# AguaC.net
KiCad netlist of a schematic drawn in EAGLE
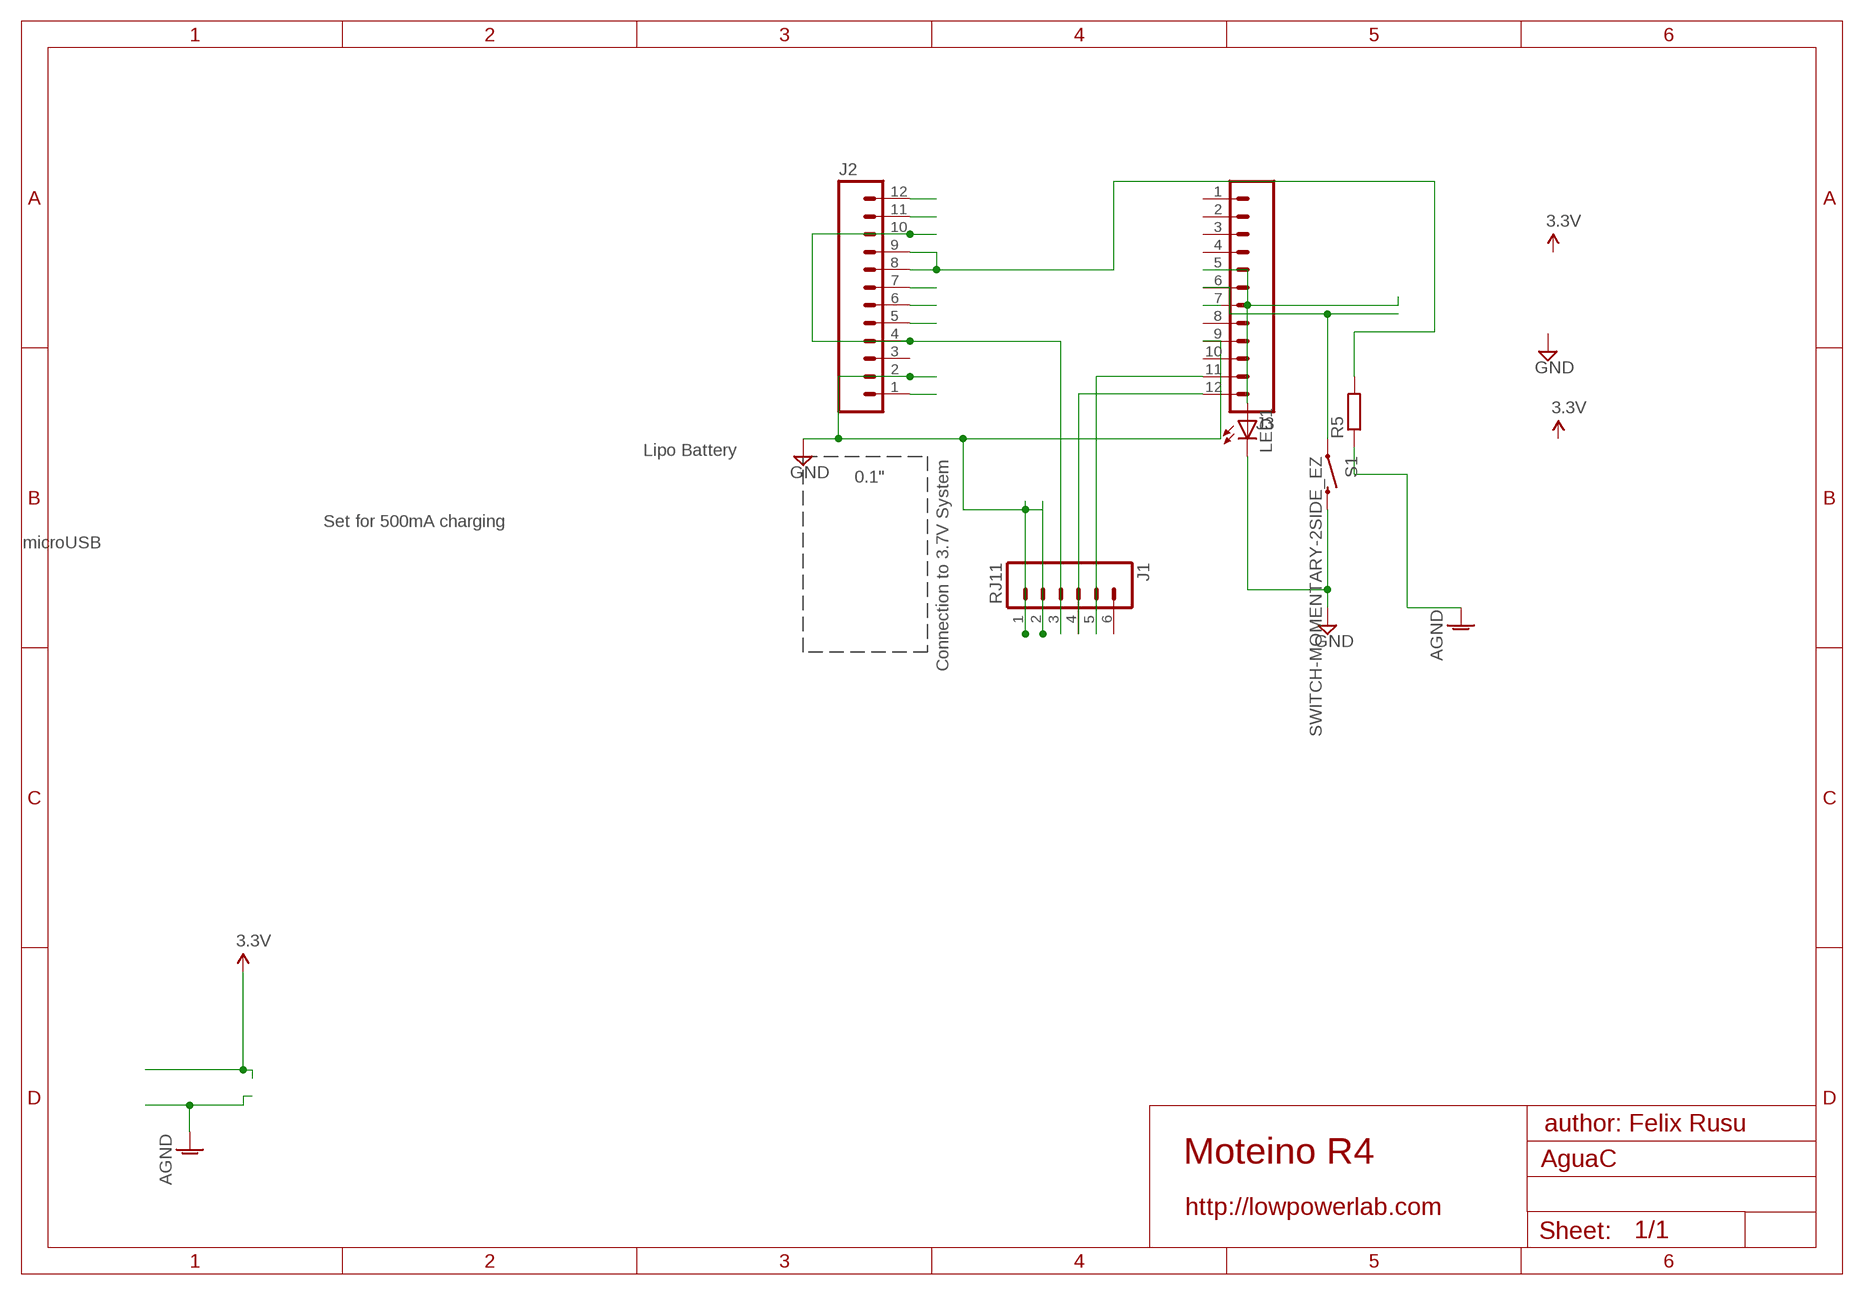
[diagram p0: schematic, sheet 1]

(export (version "E")
  (design (tool "Eeschema 10.0.6"))
  (components
    (comp (ref "J1")
      (value "RJ11")
      (footprint "eagle-import:RJ11-6")
      (libsource (lib "eagle-import") (part "RJ11-6PTH"))
    )
    (comp (ref "J2")
      (value "M12PTH")
      (footprint "eagle-import:1X12")
      (libsource (lib "eagle-import") (part "M12PTH"))
    )
    (comp (ref "J3")
      (value "M12PTH")
      (footprint "eagle-import:1X12")
      (libsource (lib "eagle-import") (part "M12PTH"))
    )
    (comp (ref "LED1")
      (value "LED3MM")
      (footprint "eagle-import:LED3MM")
      (libsource (lib "eagle-import") (part "LED3MM"))
    )
    (comp (ref "R5")
      (value "R-EU_0204/7")
      (footprint "eagle-import:0204_7")
      (libsource (lib "eagle-import") (part "R-EU_0204/7"))
    )
    (comp (ref "S1")
      (value "SWITCH-MOMENTARY-2SIDE_EZ")
      (footprint "eagle-import:TACTILE-PTH-SIDEEZ")
      (libsource (lib "eagle-import") (part "SWITCH-MOMENTARY-2SIDE_EZ"))
    )
  )
  (nets
    (net (code "2") (name "AGND") (class "Default")
      (node (ref "R5") (pin "1") (pinfunction "1_1") (pintype "passive"))
    )
    (net (code "3") (name "GND") (class "Default")
      (node (ref "J1") (pin "1") (pinfunction "1_1") (pintype "passive"))
      (node (ref "J1") (pin "2") (pinfunction "2_2") (pintype "passive"))
      (node (ref "J2") (pin "2") (pinfunction "2_2") (pintype "passive"))
      (node (ref "J3") (pin "9") (pinfunction "9_9") (pintype "passive"))
      (node (ref "LED1") (pin "K") (pinfunction "C_K") (pintype "passive"))
      (node (ref "S1") (pin "2") (pinfunction "2_2") (pintype "passive"))
    )
    (net (code "4") (name "Net-(J1-Pad3)") (class "Default")
      (node (ref "J1") (pin "3") (pinfunction "3_3") (pintype "passive"))
      (node (ref "J2") (pin "10") (pinfunction "10_10") (pintype "passive"))
      (node (ref "J2") (pin "4") (pinfunction "4_4") (pintype "passive"))
    )
    (net (code "5") (name "Net-(J1-Pad4)") (class "Default")
      (node (ref "J1") (pin "4") (pinfunction "4_4") (pintype "passive"))
      (node (ref "J3") (pin "12") (pinfunction "12_12") (pintype "passive"))
    )
    (net (code "6") (name "Net-(J1-Pad5)") (class "Default")
      (node (ref "J1") (pin "5") (pinfunction "5_5") (pintype "passive"))
      (node (ref "J3") (pin "11") (pinfunction "11_11") (pintype "passive"))
    )
    (net (code "7") (name "Net-(J2-Pad8)") (class "Default")
      (node (ref "J2") (pin "8") (pinfunction "8_8") (pintype "passive"))
      (node (ref "J2") (pin "9") (pinfunction "9_9") (pintype "passive"))
      (node (ref "R5") (pin "2") (pinfunction "2_2") (pintype "passive"))
    )
    (net (code "8") (name "Net-(J3-Pad5)") (class "Default")
      (node (ref "J3") (pin "5") (pinfunction "5_5") (pintype "passive"))
      (node (ref "LED1") (pin "A") (pinfunction "A_A") (pintype "passive"))
    )
    (net (code "9") (name "Net-(J3-Pad6)") (class "Default")
      (node (ref "J3") (pin "6") (pinfunction "6_6") (pintype "passive"))
      (node (ref "S1") (pin "1") (pinfunction "1_1") (pintype "passive"))
    )
    (net (code "10") (name "unconnected-(J1-Pad6)") (class "Default")
      (node (ref "J1") (pin "6") (pinfunction "6_6") (pintype "passive"))
    )
    (net (code "11") (name "unconnected-(J2-Pad1)") (class "Default")
      (node (ref "J2") (pin "1") (pinfunction "1_1") (pintype "passive"))
    )
    (net (code "12") (name "unconnected-(J2-Pad3)") (class "Default")
      (node (ref "J2") (pin "3") (pinfunction "3_3") (pintype "passive"))
    )
    (net (code "13") (name "unconnected-(J2-Pad5)") (class "Default")
      (node (ref "J2") (pin "5") (pinfunction "5_5") (pintype "passive"))
    )
    (net (code "14") (name "unconnected-(J2-Pad6)") (class "Default")
      (node (ref "J2") (pin "6") (pinfunction "6_6") (pintype "passive"))
    )
    (net (code "15") (name "unconnected-(J2-Pad7)") (class "Default")
      (node (ref "J2") (pin "7") (pinfunction "7_7") (pintype "passive"))
    )
    (net (code "16") (name "unconnected-(J2-Pad11)") (class "Default")
      (node (ref "J2") (pin "11") (pinfunction "11_11") (pintype "passive"))
    )
    (net (code "17") (name "unconnected-(J2-Pad12)") (class "Default")
      (node (ref "J2") (pin "12") (pinfunction "12_12") (pintype "passive"))
    )
    (net (code "18") (name "unconnected-(J3-Pad1)") (class "Default")
      (node (ref "J3") (pin "1") (pinfunction "1_1") (pintype "passive"))
    )
    (net (code "19") (name "unconnected-(J3-Pad2)") (class "Default")
      (node (ref "J3") (pin "2") (pinfunction "2_2") (pintype "passive"))
    )
    (net (code "20") (name "unconnected-(J3-Pad3)") (class "Default")
      (node (ref "J3") (pin "3") (pinfunction "3_3") (pintype "passive"))
    )
    (net (code "21") (name "unconnected-(J3-Pad4)") (class "Default")
      (node (ref "J3") (pin "4") (pinfunction "4_4") (pintype "passive"))
    )
    (net (code "22") (name "unconnected-(J3-Pad7)") (class "Default")
      (node (ref "J3") (pin "7") (pinfunction "7_7") (pintype "passive"))
    )
    (net (code "23") (name "unconnected-(J3-Pad8)") (class "Default")
      (node (ref "J3") (pin "8") (pinfunction "8_8") (pintype "passive"))
    )
    (net (code "24") (name "unconnected-(J3-Pad10)") (class "Default")
      (node (ref "J3") (pin "10") (pinfunction "10_10") (pintype "passive"))
    )
  )
)
